# motor_controller_single.net
KiCad netlist of a schematic drawn in EAGLE
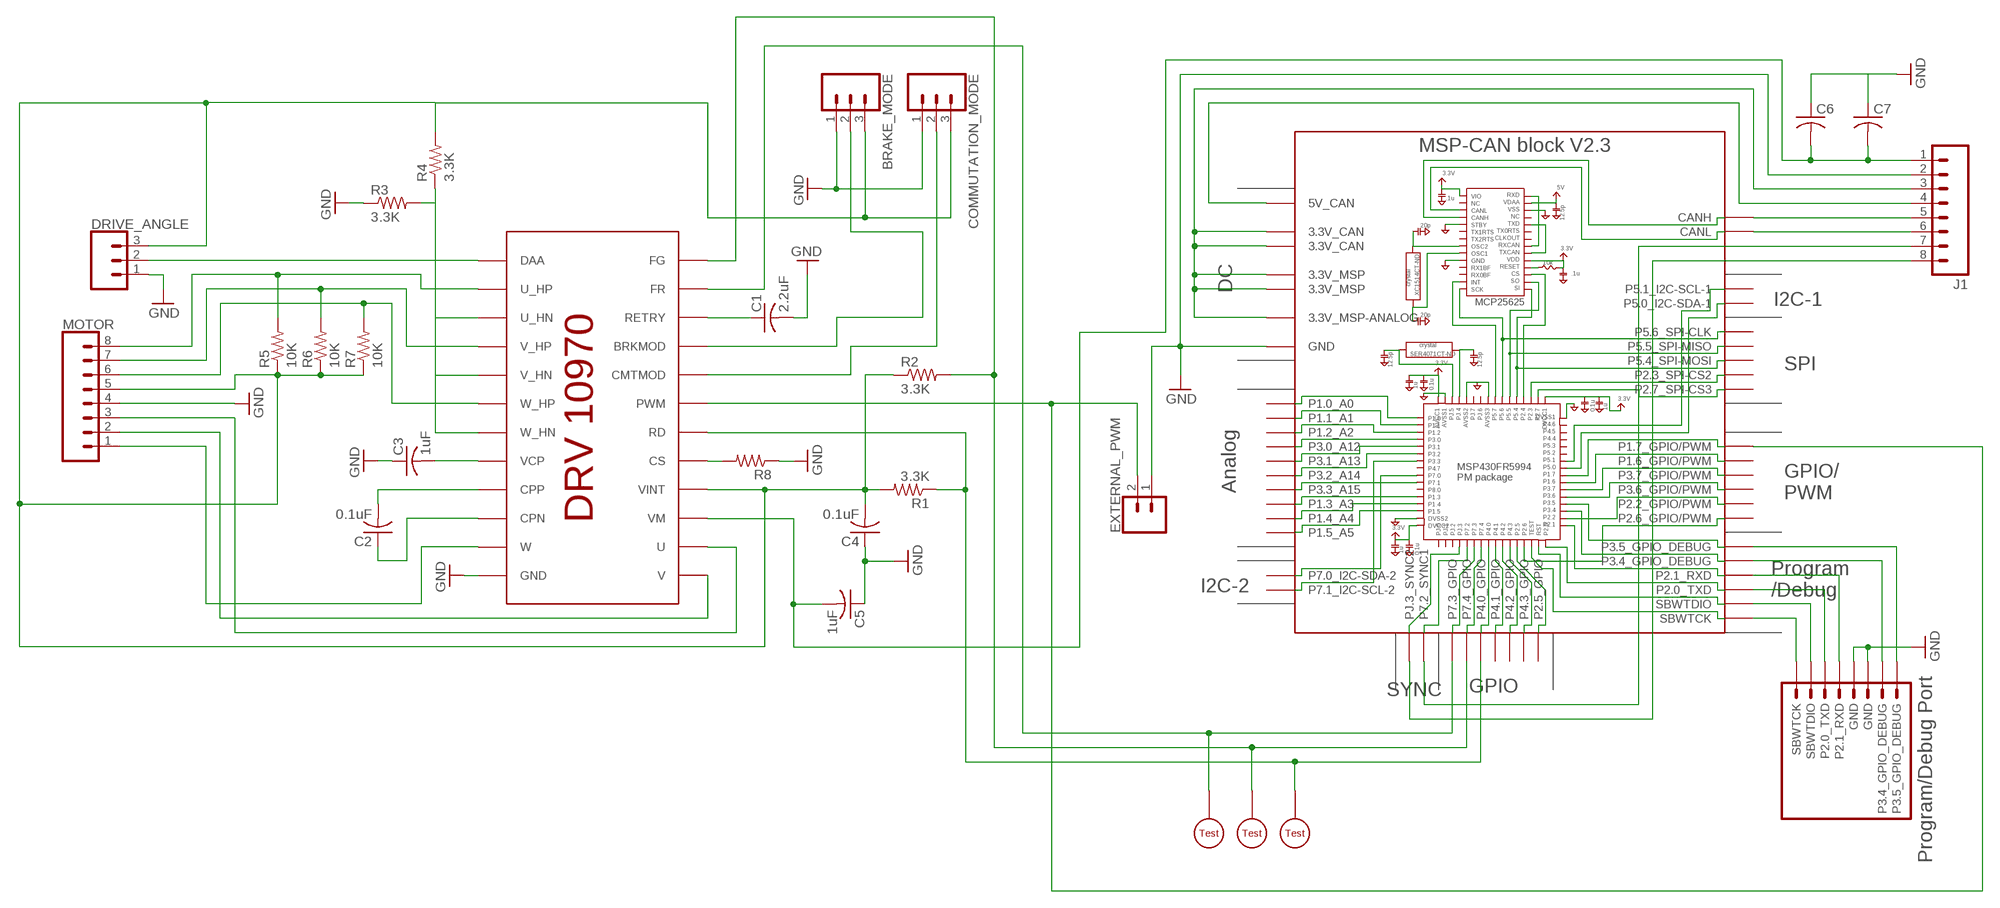
[diagram p0: schematic, sheet 1]

(export (version "E")
  (design (tool "Eeschema 10.0.6"))
  (components
    (comp (ref "BRAKE_MODE")
      (value "CONN_03LOCK")
      (footprint "eagle-import:1X03_LOCK")
      (libsource (lib "eagle-import") (part "CONN_03LOCK"))
    )
    (comp (ref "C1")
      (value "2.2uF")
      (footprint "eagle-import:C1206")
      (libsource (lib "eagle-import") (part "C-USC1206"))
    )
    (comp (ref "C2")
      (value "0.1uF")
      (footprint "eagle-import:C0805")
      (libsource (lib "eagle-import") (part "C-USC0805"))
    )
    (comp (ref "C3")
      (value "1uF")
      (footprint "eagle-import:C1206")
      (libsource (lib "eagle-import") (part "C-USC1206"))
    )
    (comp (ref "C4")
      (value "0.1uF")
      (footprint "eagle-import:C0805")
      (libsource (lib "eagle-import") (part "C-USC0805"))
    )
    (comp (ref "C5")
      (value "1uF")
      (footprint "eagle-import:C1206")
      (libsource (lib "eagle-import") (part "C-USC1206"))
    )
    (comp (ref "C6")
      (value "C-USC0805")
      (footprint "eagle-import:C0805")
      (libsource (lib "eagle-import") (part "C-USC0805"))
    )
    (comp (ref "C7")
      (value "C-USC0805")
      (footprint "eagle-import:C0805")
      (libsource (lib "eagle-import") (part "C-USC0805"))
    )
    (comp (ref "COMMUTATION_MODE")
      (value "CONN_03LOCK")
      (footprint "eagle-import:1X03_LOCK")
      (libsource (lib "eagle-import") (part "CONN_03LOCK"))
    )
    (comp (ref "DRIVE_ANGLE")
      (value "CONN_03LOCK")
      (footprint "eagle-import:1X03_LOCK")
      (libsource (lib "eagle-import") (part "CONN_03LOCK"))
    )
    (comp (ref "EXTERNAL_PWM")
      (value "CONN_02LOCK")
      (footprint "eagle-import:1X02_LOCK")
      (libsource (lib "eagle-import") (part "CONN_02LOCK"))
    )
    (comp (ref "J1")
      (value "M08LOCK")
      (footprint "eagle-import:1X08_LOCK")
      (libsource (lib "eagle-import") (part "M08LOCK"))
    )
    (comp (ref "MOTOR")
      (value "CONN_08\"")
      (footprint "eagle-import:1X08@1")
      (libsource (lib "eagle-import") (part "CONN_08{dblquote}"))
    )
    (comp (ref "R1")
      (value "3.3K")
      (footprint "eagle-import:R0805")
      (libsource (lib "eagle-import") (part "R-US_R0805"))
    )
    (comp (ref "R2")
      (value "3.3K")
      (footprint "eagle-import:R0805")
      (libsource (lib "eagle-import") (part "R-US_R0805"))
    )
    (comp (ref "R3")
      (value "3.3K")
      (footprint "eagle-import:R0805")
      (libsource (lib "eagle-import") (part "R-US_R0805"))
    )
    (comp (ref "R4")
      (value "3.3K")
      (footprint "eagle-import:R0805")
      (libsource (lib "eagle-import") (part "R-US_R0805"))
    )
    (comp (ref "R5")
      (value "10K")
      (footprint "eagle-import:R0805")
      (libsource (lib "eagle-import") (part "R-US_R0805"))
    )
    (comp (ref "R6")
      (value "10K")
      (footprint "eagle-import:R0805")
      (libsource (lib "eagle-import") (part "R-US_R0805"))
    )
    (comp (ref "R7")
      (value "10K")
      (footprint "eagle-import:R0805")
      (libsource (lib "eagle-import") (part "R-US_R0805"))
    )
    (comp (ref "R8")
      (value "R-US_R0805")
      (footprint "eagle-import:R0805")
      (libsource (lib "eagle-import") (part "R-US_R0805"))
    )
    (comp (ref "U$1")
      (value "DRV10970")
      (footprint "eagle-import:DRV10970")
      (libsource (lib "eagle-import") (part "DRV10970"))
    )
    (comp (ref "U$2")
      (value "MSP-CAN_BLOCK")
      (footprint "eagle-import:MSP-CAN_BLOCK")
      (libsource (lib "eagle-import") (part "MSP-CAN_BLOCK"))
    )
    (comp (ref "U$3")
      (value "PROGRAM/DEBUG_PORT")
      (footprint "eagle-import:1X08_CONNECTOR")
      (libsource (lib "eagle-import") (part "PROGRAM/DEBUG_PORT"))
    )
    (comp (ref "U$4")
      (value "KEYSTONE_SMD_TEST_POINT")
      (footprint "eagle-import:KEYSTONE_SMD_TEST_POINT")
      (libsource (lib "eagle-import") (part "KEYSTONE_SMD_TEST_POINT"))
    )
    (comp (ref "U$5")
      (value "KEYSTONE_SMD_TEST_POINT")
      (footprint "eagle-import:KEYSTONE_SMD_TEST_POINT")
      (libsource (lib "eagle-import") (part "KEYSTONE_SMD_TEST_POINT"))
    )
    (comp (ref "U$6")
      (value "KEYSTONE_SMD_TEST_POINT")
      (footprint "eagle-import:KEYSTONE_SMD_TEST_POINT")
      (libsource (lib "eagle-import") (part "KEYSTONE_SMD_TEST_POINT"))
    )
  )
  (nets
    (net (code "1") (name "GND") (class "Default")
      (node (ref "BRAKE_MODE") (pin "1") (pinfunction "1_1") (pintype "passive"))
      (node (ref "C1") (pin "2") (pinfunction "2_2") (pintype "passive"))
      (node (ref "C3") (pin "1") (pinfunction "1_1") (pintype "passive"))
      (node (ref "C4") (pin "1") (pinfunction "1_1") (pintype "passive"))
      (node (ref "C5") (pin "1") (pinfunction "1_1") (pintype "passive"))
      (node (ref "C6") (pin "1") (pinfunction "1_1") (pintype "passive"))
      (node (ref "C7") (pin "1") (pinfunction "1_1") (pintype "passive"))
      (node (ref "COMMUTATION_MODE") (pin "1") (pinfunction "1_1") (pintype "passive"))
      (node (ref "DRIVE_ANGLE") (pin "1") (pinfunction "1_1") (pintype "passive"))
      (node (ref "EXTERNAL_PWM") (pin "1") (pinfunction "1_1") (pintype "passive"))
      (node (ref "J1") (pin "2") (pinfunction "2_2") (pintype "passive"))
      (node (ref "MOTOR") (pin "4") (pinfunction "4_4") (pintype "passive"))
      (node (ref "R3") (pin "1") (pinfunction "1_1") (pintype "passive"))
      (node (ref "R8") (pin "1") (pinfunction "1_1") (pintype "passive"))
      (node (ref "U$1") (pin "GND@1") (pinfunction "GND_GND@1") (pintype "bidirectional"))
      (node (ref "U$1") (pin "GND@2") (pinfunction "GND_GND@2") (pintype "bidirectional"))
      (node (ref "U$2") (pin "GND@1") (pinfunction "GND_GND@1") (pintype "bidirectional"))
      (node (ref "U$2") (pin "GND@10") (pinfunction "GND_GND@10") (pintype "bidirectional"))
      (node (ref "U$2") (pin "GND@11") (pinfunction "GND_GND@11") (pintype "bidirectional"))
      (node (ref "U$2") (pin "GND@12") (pinfunction "GND_GND@12") (pintype "bidirectional"))
      (node (ref "U$2") (pin "GND@13") (pinfunction "GND_GND@13") (pintype "bidirectional"))
      (node (ref "U$2") (pin "GND@14") (pinfunction "GND_GND@14") (pintype "bidirectional"))
      (node (ref "U$2") (pin "GND@15") (pinfunction "GND_GND@15") (pintype "bidirectional"))
      (node (ref "U$2") (pin "GND@16") (pinfunction "GND_GND@16") (pintype "bidirectional"))
      (node (ref "U$2") (pin "GND@17") (pinfunction "GND_GND@17") (pintype "bidirectional"))
      (node (ref "U$2") (pin "GND@2") (pinfunction "GND_GND@2") (pintype "bidirectional"))
      (node (ref "U$2") (pin "GND@26") (pinfunction "GND_GND@26") (pintype "bidirectional"))
      (node (ref "U$2") (pin "GND@3") (pinfunction "GND_GND@3") (pintype "bidirectional"))
      (node (ref "U$2") (pin "GND@4") (pinfunction "GND_GND@4") (pintype "bidirectional"))
      (node (ref "U$2") (pin "GND@5") (pinfunction "GND_GND@5") (pintype "bidirectional"))
      (node (ref "U$2") (pin "GND@7") (pinfunction "GND_GND@7") (pintype "bidirectional"))
      (node (ref "U$2") (pin "GND@8") (pinfunction "GND_GND@8") (pintype "bidirectional"))
      (node (ref "U$2") (pin "GND@9") (pinfunction "GND_GND@9") (pintype "bidirectional"))
      (node (ref "U$3") (pin "5") (pinfunction "GND_5") (pintype "bidirectional"))
      (node (ref "U$3") (pin "6") (pinfunction "GND_6") (pintype "bidirectional"))
    )
    (net (code "2") (name "Net-(BRAKE_MODE-Pad2)") (class "Default")
      (node (ref "BRAKE_MODE") (pin "2") (pinfunction "2_2") (pintype "passive"))
      (node (ref "U$1") (pin "BRKMOD") (pinfunction "BRKMOD_BRKMOD") (pintype "bidirectional"))
    )
    (net (code "3") (name "Net-(BRAKE_MODE-Pad3)") (class "Default")
      (node (ref "BRAKE_MODE") (pin "3") (pinfunction "3_3") (pintype "passive"))
      (node (ref "C4") (pin "2") (pinfunction "2_2") (pintype "passive"))
      (node (ref "COMMUTATION_MODE") (pin "3") (pinfunction "3_3") (pintype "passive"))
      (node (ref "DRIVE_ANGLE") (pin "3") (pinfunction "3_3") (pintype "passive"))
      (node (ref "MOTOR") (pin "5") (pinfunction "5_5") (pintype "passive"))
      (node (ref "R1") (pin "2") (pinfunction "2_2") (pintype "passive"))
      (node (ref "R2") (pin "1") (pinfunction "1_1") (pintype "passive"))
      (node (ref "R4") (pin "2") (pinfunction "2_2") (pintype "passive"))
      (node (ref "R5") (pin "1") (pinfunction "1_1") (pintype "passive"))
      (node (ref "R6") (pin "1") (pinfunction "1_1") (pintype "passive"))
      (node (ref "R7") (pin "1") (pinfunction "1_1") (pintype "passive"))
      (node (ref "U$1") (pin "VINT") (pinfunction "VINT_VINT") (pintype "bidirectional"))
    )
    (net (code "4") (name "Net-(C1-Pad1)") (class "Default")
      (node (ref "C1") (pin "1") (pinfunction "1_1") (pintype "passive"))
      (node (ref "U$1") (pin "RETRY") (pinfunction "RETRY_RETRY") (pintype "bidirectional"))
    )
    (net (code "5") (name "Net-(C2-Pad1)") (class "Default")
      (node (ref "C2") (pin "1") (pinfunction "1_1") (pintype "passive"))
      (node (ref "U$1") (pin "CPN") (pinfunction "CPN_CPN") (pintype "bidirectional"))
    )
    (net (code "6") (name "Net-(C2-Pad2)") (class "Default")
      (node (ref "C2") (pin "2") (pinfunction "2_2") (pintype "passive"))
      (node (ref "U$1") (pin "CPP") (pinfunction "CPP_CPP") (pintype "bidirectional"))
    )
    (net (code "7") (name "Net-(C3-Pad2)") (class "Default")
      (node (ref "C3") (pin "2") (pinfunction "2_2") (pintype "passive"))
      (node (ref "U$1") (pin "VCP") (pinfunction "VCP_VCP") (pintype "bidirectional"))
    )
    (net (code "8") (name "Net-(C5-Pad2)") (class "Default")
      (node (ref "C5") (pin "2") (pinfunction "2_2") (pintype "passive"))
      (node (ref "C6") (pin "2") (pinfunction "2_2") (pintype "passive"))
      (node (ref "C7") (pin "2") (pinfunction "2_2") (pintype "passive"))
      (node (ref "J1") (pin "1") (pinfunction "1_1") (pintype "passive"))
      (node (ref "U$1") (pin "VM") (pinfunction "VM_VM") (pintype "bidirectional"))
    )
    (net (code "9") (name "Net-(COMMUTATION_MODE-Pad2)") (class "Default")
      (node (ref "COMMUTATION_MODE") (pin "2") (pinfunction "2_2") (pintype "passive"))
      (node (ref "U$1") (pin "CMTMOD") (pinfunction "CMTMOD_CMTMOD") (pintype "bidirectional"))
    )
    (net (code "10") (name "Net-(DRIVE_ANGLE-Pad2)") (class "Default")
      (node (ref "DRIVE_ANGLE") (pin "2") (pinfunction "2_2") (pintype "passive"))
      (node (ref "U$1") (pin "DAA") (pinfunction "DAA_DAA") (pintype "bidirectional"))
    )
    (net (code "11") (name "Net-(EXTERNAL_PWM-Pad2)") (class "Default")
      (node (ref "EXTERNAL_PWM") (pin "2") (pinfunction "2_2") (pintype "passive"))
      (node (ref "U$1") (pin "PWM") (pinfunction "PWM_PWM") (pintype "bidirectional"))
      (node (ref "U$2") (pin "P1.7_GPIO/PWM") (pinfunction "P1.7_GPIO/PWM_P1.7_GPIO/PWM") (pintype "bidirectional"))
    )
    (net (code "12") (name "Net-(J1-Pad5)") (class "Default")
      (node (ref "J1") (pin "5") (pinfunction "5_5") (pintype "passive"))
      (node (ref "U$2") (pin "CANH") (pinfunction "CANH_CANH") (pintype "bidirectional"))
    )
    (net (code "13") (name "Net-(J1-Pad6)") (class "Default")
      (node (ref "J1") (pin "6") (pinfunction "6_6") (pintype "passive"))
      (node (ref "U$2") (pin "CANL") (pinfunction "CANL_CANL") (pintype "bidirectional"))
    )
    (net (code "14") (name "Net-(J1-Pad7)") (class "Default")
      (node (ref "J1") (pin "7") (pinfunction "7_7") (pintype "passive"))
      (node (ref "U$2") (pin "P7.2_SYNC1") (pinfunction "P7.2_SYNC1_P7.2_SYNC1") (pintype "bidirectional"))
    )
    (net (code "15") (name "Net-(J1-Pad8)") (class "Default")
      (node (ref "J1") (pin "8") (pinfunction "8_8") (pintype "passive"))
      (node (ref "U$2") (pin "PJ.3_SYNC2") (pinfunction "PJ.3_SYNC2_PJ.3_SYNC2") (pintype "bidirectional"))
    )
    (net (code "16") (name "Net-(MOTOR-Pad1)") (class "Default")
      (node (ref "MOTOR") (pin "1") (pinfunction "1_1") (pintype "passive"))
      (node (ref "U$1") (pin "W") (pinfunction "W_W") (pintype "bidirectional"))
    )
    (net (code "17") (name "Net-(MOTOR-Pad2)") (class "Default")
      (node (ref "MOTOR") (pin "2") (pinfunction "2_2") (pintype "passive"))
      (node (ref "U$1") (pin "V") (pinfunction "V_V") (pintype "bidirectional"))
    )
    (net (code "18") (name "Net-(MOTOR-Pad3)") (class "Default")
      (node (ref "MOTOR") (pin "3") (pinfunction "3_3") (pintype "passive"))
      (node (ref "U$1") (pin "U") (pinfunction "U_U") (pintype "bidirectional"))
    )
    (net (code "19") (name "Net-(MOTOR-Pad6)") (class "Default")
      (node (ref "MOTOR") (pin "6") (pinfunction "6_6") (pintype "passive"))
      (node (ref "R7") (pin "2") (pinfunction "2_2") (pintype "passive"))
      (node (ref "U$1") (pin "W_HP") (pinfunction "W_HP_W_HP") (pintype "bidirectional"))
    )
    (net (code "20") (name "Net-(MOTOR-Pad7)") (class "Default")
      (node (ref "MOTOR") (pin "7") (pinfunction "7_7") (pintype "passive"))
      (node (ref "R6") (pin "2") (pinfunction "2_2") (pintype "passive"))
      (node (ref "U$1") (pin "V_HP") (pinfunction "V_HP_V_HP") (pintype "bidirectional"))
    )
    (net (code "21") (name "Net-(MOTOR-Pad8)") (class "Default")
      (node (ref "MOTOR") (pin "8") (pinfunction "8_8") (pintype "passive"))
      (node (ref "R5") (pin "2") (pinfunction "2_2") (pintype "passive"))
      (node (ref "U$1") (pin "U_HP") (pinfunction "U_HP_U_HP") (pintype "bidirectional"))
    )
    (net (code "22") (name "Net-(R1-Pad1)") (class "Default")
      (node (ref "R1") (pin "1") (pinfunction "1_1") (pintype "passive"))
      (node (ref "U$1") (pin "RD") (pinfunction "RD_RD") (pintype "bidirectional"))
      (node (ref "U$2") (pin "P4.0_GPIO") (pinfunction "P4.0_GPIO_P4.0_GPIO") (pintype "bidirectional"))
      (node (ref "U$6") (pin "P$1") (pinfunction "P$1_P$1") (pintype "bidirectional"))
    )
    (net (code "23") (name "Net-(R2-Pad2)") (class "Default")
      (node (ref "R2") (pin "2") (pinfunction "2_2") (pintype "passive"))
      (node (ref "U$1") (pin "FG") (pinfunction "FG_FG") (pintype "bidirectional"))
      (node (ref "U$2") (pin "P7.4_GPIO") (pinfunction "P7.4_GPIO_P7.4_GPIO") (pintype "bidirectional"))
      (node (ref "U$5") (pin "P$1") (pinfunction "P$1_P$1") (pintype "bidirectional"))
    )
    (net (code "24") (name "Net-(R3-Pad2)") (class "Default")
      (node (ref "R3") (pin "2") (pinfunction "2_2") (pintype "passive"))
      (node (ref "R4") (pin "1") (pinfunction "1_1") (pintype "passive"))
      (node (ref "U$1") (pin "U_HN") (pinfunction "U_HN_U_HN") (pintype "bidirectional"))
      (node (ref "U$1") (pin "V_HN") (pinfunction "V_HN_V_HN") (pintype "bidirectional"))
      (node (ref "U$1") (pin "W_HN") (pinfunction "W_HN_W_HN") (pintype "bidirectional"))
    )
    (net (code "25") (name "Net-(R8-Pad2)") (class "Default")
      (node (ref "R8") (pin "2") (pinfunction "2_2") (pintype "passive"))
      (node (ref "U$1") (pin "CS") (pinfunction "CS_CS") (pintype "bidirectional"))
    )
    (net (code "26") (name "Net-(U$1-PadFR)") (class "Default")
      (node (ref "U$1") (pin "FR") (pinfunction "FR_FR") (pintype "bidirectional"))
      (node (ref "U$2") (pin "P7.3_GPIO") (pinfunction "P7.3_GPIO_P7.3_GPIO") (pintype "bidirectional"))
      (node (ref "U$4") (pin "P$1") (pinfunction "P$1_P$1") (pintype "bidirectional"))
    )
    (net (code "27") (name "Net-(U$2-3.3V_MSP-ANALOG)") (class "Default")
      (node (ref "J1") (pin "3") (pinfunction "3_3") (pintype "passive"))
      (node (ref "U$2") (pin "3.3V@CAN1") (pinfunction "3.3V_CAN_3.3V@CAN1") (pintype "bidirectional"))
      (node (ref "U$2") (pin "3.3V@CAN2") (pinfunction "3.3V_CAN_3.3V@CAN2") (pintype "bidirectional"))
      (node (ref "U$2") (pin "3.3V@MSP1") (pinfunction "3.3V_MSP_3.3V@MSP1") (pintype "bidirectional"))
      (node (ref "U$2") (pin "3.3V@MSP2") (pinfunction "3.3V_MSP_3.3V@MSP2") (pintype "bidirectional"))
      (node (ref "U$2") (pin "3.3V_ANALOG@MSP2") (pinfunction "3.3V_MSP-ANALOG_3.3V_ANALOG@MSP2") (pintype "bidirectional"))
    )
    (net (code "28") (name "Net-(U$2-5V_CAN)") (class "Default")
      (node (ref "J1") (pin "4") (pinfunction "4_4") (pintype "passive"))
      (node (ref "U$2") (pin "5V") (pinfunction "5V_CAN_5V") (pintype "bidirectional"))
    )
    (net (code "29") (name "Net-(U$2-PadSBWTCK)") (class "Default")
      (node (ref "U$2") (pin "SBWTCK") (pinfunction "SBWTCK_SBWTCK") (pintype "bidirectional"))
      (node (ref "U$3") (pin "SBWTCK") (pinfunction "SBWTCK_SBWTCK") (pintype "bidirectional"))
    )
    (net (code "30") (name "Net-(U$3-P2.0_TXD)") (class "Default")
      (node (ref "U$2") (pin "P2.0_TXD") (pinfunction "P2.0_TXD_P2.0_TXD") (pintype "bidirectional"))
      (node (ref "U$3") (pin "3") (pinfunction "P2.0_TXD_3") (pintype "bidirectional"))
    )
    (net (code "31") (name "Net-(U$3-P2.1_RXD)") (class "Default")
      (node (ref "U$2") (pin "P2.1_RXD") (pinfunction "P2.1_RXD_P2.1_RXD") (pintype "bidirectional"))
      (node (ref "U$3") (pin "4") (pinfunction "P2.1_RXD_4") (pintype "bidirectional"))
    )
    (net (code "32") (name "Net-(U$3-P3.4_GPIO_DEBUG)") (class "Default")
      (node (ref "U$2") (pin "P3.4_GPIO_DEBUG") (pinfunction "P3.4_GPIO_DEBUG_P3.4_GPIO_DEBUG") (pintype "bidirectional"))
      (node (ref "U$3") (pin "7") (pinfunction "P3.4_GPIO_DEBUG_7") (pintype "bidirectional"))
    )
    (net (code "33") (name "Net-(U$3-P3.5_GPIO_DEBUG)") (class "Default")
      (node (ref "U$2") (pin "P3.5_GPIO_DEBUG") (pinfunction "P3.5_GPIO_DEBUG_P3.5_GPIO_DEBUG") (pintype "bidirectional"))
      (node (ref "U$3") (pin "8") (pinfunction "P3.5_GPIO_DEBUG_8") (pintype "bidirectional"))
    )
    (net (code "34") (name "Net-(U$3-SBWTDIO)") (class "Default")
      (node (ref "U$2") (pin "SBWTDIO") (pinfunction "SBWTDIO_SBWTDIO") (pintype "bidirectional"))
      (node (ref "U$3") (pin "2") (pinfunction "SBWTDIO_2") (pintype "bidirectional"))
    )
    (net (code "35") (name "unconnected-(U$2-P2.3_SPI-CS2-PadP2.4_SPI-CS2)") (class "Default")
      (node (ref "U$2") (pin "P2.4_SPI-CS2") (pinfunction "P2.3_SPI-CS2_P2.4_SPI-CS2") (pintype "bidirectional"))
    )
    (net (code "36") (name "unconnected-(U$2-PadP1.0_A0)") (class "Default")
      (node (ref "U$2") (pin "P1.0_A0") (pinfunction "P1.0_A0_P1.0_A0") (pintype "bidirectional"))
    )
    (net (code "37") (name "unconnected-(U$2-PadP1.1_A1)") (class "Default")
      (node (ref "U$2") (pin "P1.1_A1") (pinfunction "P1.1_A1_P1.1_A1") (pintype "bidirectional"))
    )
    (net (code "38") (name "unconnected-(U$2-PadP1.2_A2)") (class "Default")
      (node (ref "U$2") (pin "P1.2_A2") (pinfunction "P1.2_A2_P1.2_A2") (pintype "bidirectional"))
    )
    (net (code "39") (name "unconnected-(U$2-PadP1.3_A3)") (class "Default")
      (node (ref "U$2") (pin "P1.3_A3") (pinfunction "P1.3_A3_P1.3_A3") (pintype "bidirectional"))
    )
    (net (code "40") (name "unconnected-(U$2-PadP1.4_A4)") (class "Default")
      (node (ref "U$2") (pin "P1.4_A4") (pinfunction "P1.4_A4_P1.4_A4") (pintype "bidirectional"))
    )
    (net (code "41") (name "unconnected-(U$2-PadP1.5_A5)") (class "Default")
      (node (ref "U$2") (pin "P1.5_A5") (pinfunction "P1.5_A5_P1.5_A5") (pintype "bidirectional"))
    )
    (net (code "42") (name "unconnected-(U$2-PadP1.6_GPIO{slash}PWM)") (class "Default")
      (node (ref "U$2") (pin "P1.6_GPIO/PWM") (pinfunction "P1.6_GPIO/PWM_P1.6_GPIO/PWM") (pintype "bidirectional"))
    )
    (net (code "43") (name "unconnected-(U$2-PadP2.2_GPIO{slash}PWM)") (class "Default")
      (node (ref "U$2") (pin "P2.2_GPIO/PWM") (pinfunction "P2.2_GPIO/PWM_P2.2_GPIO/PWM") (pintype "bidirectional"))
    )
    (net (code "44") (name "unconnected-(U$2-PadP2.5_GPIO)") (class "Default")
      (node (ref "U$2") (pin "P2.5_GPIO") (pinfunction "P2.5_GPIO_P2.5_GPIO") (pintype "bidirectional"))
    )
    (net (code "45") (name "unconnected-(U$2-PadP2.6_GPIO{slash}PWM)") (class "Default")
      (node (ref "U$2") (pin "P2.6_GPIO/PWM") (pinfunction "P2.6_GPIO/PWM_P2.6_GPIO/PWM") (pintype "bidirectional"))
    )
    (net (code "46") (name "unconnected-(U$2-PadP2.7_SPI-CS3)") (class "Default")
      (node (ref "U$2") (pin "P2.7_SPI-CS3") (pinfunction "P2.7_SPI-CS3_P2.7_SPI-CS3") (pintype "bidirectional"))
    )
    (net (code "47") (name "unconnected-(U$2-PadP3.0_A12)") (class "Default")
      (node (ref "U$2") (pin "P3.0_A12") (pinfunction "P3.0_A12_P3.0_A12") (pintype "bidirectional"))
    )
    (net (code "48") (name "unconnected-(U$2-PadP3.1_A13)") (class "Default")
      (node (ref "U$2") (pin "P3.1_A13") (pinfunction "P3.1_A13_P3.1_A13") (pintype "bidirectional"))
    )
    (net (code "49") (name "unconnected-(U$2-PadP3.2_A14)") (class "Default")
      (node (ref "U$2") (pin "P3.2_A14") (pinfunction "P3.2_A14_P3.2_A14") (pintype "bidirectional"))
    )
    (net (code "50") (name "unconnected-(U$2-PadP3.3_A15)") (class "Default")
      (node (ref "U$2") (pin "P3.3_A15") (pinfunction "P3.3_A15_P3.3_A15") (pintype "bidirectional"))
    )
    (net (code "51") (name "unconnected-(U$2-PadP3.6_GPIO{slash}PWM)") (class "Default")
      (node (ref "U$2") (pin "P3.6_GPIO/PWM") (pinfunction "P3.6_GPIO/PWM_P3.6_GPIO/PWM") (pintype "bidirectional"))
    )
    (net (code "52") (name "unconnected-(U$2-PadP3.7_GPIO{slash}PWM)") (class "Default")
      (node (ref "U$2") (pin "P3.7_GPIO/PWM") (pinfunction "P3.7_GPIO/PWM_P3.7_GPIO/PWM") (pintype "bidirectional"))
    )
    (net (code "53") (name "unconnected-(U$2-PadP4.1_GPIO)") (class "Default")
      (node (ref "U$2") (pin "P4.1_GPIO") (pinfunction "P4.1_GPIO_P4.1_GPIO") (pintype "bidirectional"))
    )
    (net (code "54") (name "unconnected-(U$2-PadP4.2_GPIO)") (class "Default")
      (node (ref "U$2") (pin "P4.2_GPIO") (pinfunction "P4.2_GPIO_P4.2_GPIO") (pintype "bidirectional"))
    )
    (net (code "55") (name "unconnected-(U$2-PadP4.3_GPIO)") (class "Default")
      (node (ref "U$2") (pin "P4.3_GPIO") (pinfunction "P4.3_GPIO_P4.3_GPIO") (pintype "bidirectional"))
    )
    (net (code "56") (name "unconnected-(U$2-PadP5.0_I2C-SDA-1)") (class "Default")
      (node (ref "U$2") (pin "P5.0_I2C-SDA-1") (pinfunction "P5.0_I2C-SDA-1_P5.0_I2C-SDA-1") (pintype "bidirectional"))
    )
    (net (code "57") (name "unconnected-(U$2-PadP5.1_I2C-SCL-1)") (class "Default")
      (node (ref "U$2") (pin "P5.1_I2C-SCL-1") (pinfunction "P5.1_I2C-SCL-1_P5.1_I2C-SCL-1") (pintype "bidirectional"))
    )
    (net (code "58") (name "unconnected-(U$2-PadP5.4_SPI-MOSI)") (class "Default")
      (node (ref "U$2") (pin "P5.4_SPI-MOSI") (pinfunction "P5.4_SPI-MOSI_P5.4_SPI-MOSI") (pintype "bidirectional"))
    )
    (net (code "59") (name "unconnected-(U$2-PadP5.5_SPI-MISO)") (class "Default")
      (node (ref "U$2") (pin "P5.5_SPI-MISO") (pinfunction "P5.5_SPI-MISO_P5.5_SPI-MISO") (pintype "bidirectional"))
    )
    (net (code "60") (name "unconnected-(U$2-PadP5.6_SPI-CLK)") (class "Default")
      (node (ref "U$2") (pin "P5.6_SPI-CLK") (pinfunction "P5.6_SPI-CLK_P5.6_SPI-CLK") (pintype "bidirectional"))
    )
    (net (code "61") (name "unconnected-(U$2-PadP7.0_I2C-SDA-2)") (class "Default")
      (node (ref "U$2") (pin "P7.0_I2C-SDA-2") (pinfunction "P7.0_I2C-SDA-2_P7.0_I2C-SDA-2") (pintype "bidirectional"))
    )
    (net (code "62") (name "unconnected-(U$2-PadP7.1_I2C-SCL-2)") (class "Default")
      (node (ref "U$2") (pin "P7.1_I2C-SCL-2") (pinfunction "P7.1_I2C-SCL-2_P7.1_I2C-SCL-2") (pintype "bidirectional"))
    )
  )
)
